# Buttons.net
KiCad netlist of a schematic drawn in Altium Designer
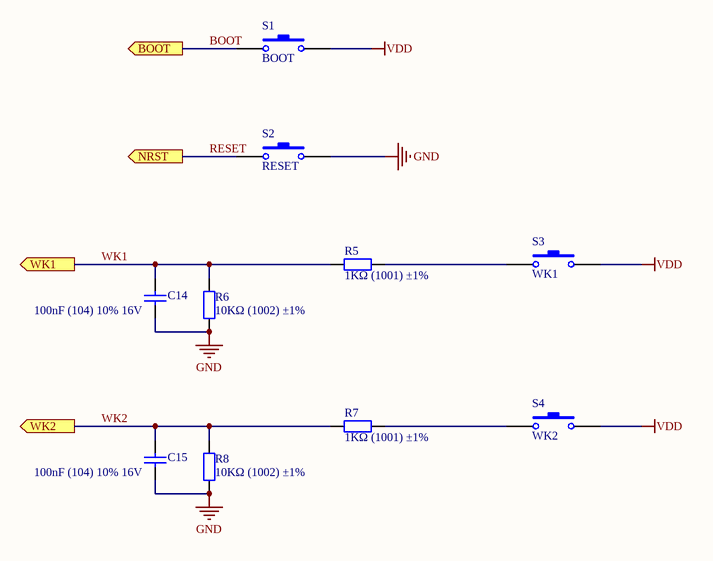
[diagram p0: Buttons.SchDoc]

(export (version "E")
  (design (tool "Eeschema 10.0.6"))
  (components
    (comp (ref "C14")
      (value "100nF (104) 10% 16V")
      (footprint "0402_C")
      (description "贴片电容")
      (libsource (lib "Miscellaneous Devices LC") (part "0402 100nF (104) 10% 16V"))
    )
    (comp (ref "C15")
      (value "100nF (104) 10% 16V")
      (footprint "0402_C")
      (description "贴片电容")
      (libsource (lib "Miscellaneous Devices LC") (part "0402 100nF (104) 10% 16V"))
    )
    (comp (ref "R5")
      (value "1KΩ (1001) ±1%")
      (footprint "0402_R")
      (description "贴片电阻")
      (libsource (lib "Miscellaneous Devices LC") (part "0402 1KΩ (1001) 1%"))
    )
    (comp (ref "R6")
      (value "10KΩ (1002) ±1%")
      (footprint "0402_R")
      (description "贴片电阻")
      (libsource (lib "Miscellaneous Devices LC") (part "0402 10KΩ (1002) 1%"))
    )
    (comp (ref "R7")
      (value "1KΩ (1001) ±1%")
      (footprint "0402_R")
      (description "贴片电阻")
      (libsource (lib "Miscellaneous Devices LC") (part "0402 1KΩ (1001) 1%"))
    )
    (comp (ref "R8")
      (value "10KΩ (1002) ±1%")
      (footprint "0402_R")
      (description "贴片电阻")
      (libsource (lib "Miscellaneous Devices LC") (part "0402 10KΩ (1002) 1%"))
    )
    (comp (ref "S1")
      (value "BOOT")
      (footprint "SW-6x6")
      (description "Switch")
      (fields (field (name "PUBLISHER") "Altium Limited"))
      (libsource (lib "Miscellaneous Devices") (part "SW-PB"))
    )
    (comp (ref "S2")
      (value "RESET")
      (footprint "SW-6x6")
      (description "Switch")
      (fields (field (name "PUBLISHER") "Altium Limited"))
      (libsource (lib "Miscellaneous Devices") (part "SW-PB"))
    )
    (comp (ref "S3")
      (value "WK1")
      (footprint "SW-6x6")
      (description "Switch")
      (fields (field (name "PUBLISHER") "Altium Limited"))
      (libsource (lib "Miscellaneous Devices") (part "SW-PB"))
    )
    (comp (ref "S4")
      (value "WK2")
      (footprint "SW-6x6")
      (description "Switch")
      (fields (field (name "PUBLISHER") "Altium Limited"))
      (libsource (lib "Miscellaneous Devices") (part "SW-PB"))
    )
  )
  (nets
    (net (code "1") (name "/BOOT") (class "Default")
      (node (ref "S1") (pin "1") (pinfunction "1_1") (pintype "passive"))
    )
    (net (code "2") (name "/RESET") (class "Default")
      (node (ref "S2") (pin "1") (pinfunction "1_1") (pintype "passive"))
    )
    (net (code "3") (name "/WK1") (class "Default")
      (node (ref "C14") (pin "2") (pinfunction "2_2") (pintype "passive"))
      (node (ref "R5") (pin "1") (pinfunction "1_1") (pintype "passive"))
      (node (ref "R6") (pin "2") (pinfunction "2_2") (pintype "passive"))
    )
    (net (code "4") (name "/WK2") (class "Default")
      (node (ref "C15") (pin "2") (pinfunction "2_2") (pintype "passive"))
      (node (ref "R7") (pin "1") (pinfunction "1_1") (pintype "passive"))
      (node (ref "R8") (pin "2") (pinfunction "2_2") (pintype "passive"))
    )
    (net (code "5") (name "GND") (class "Default")
      (node (ref "C14") (pin "1") (pinfunction "1_1") (pintype "passive"))
      (node (ref "C15") (pin "1") (pinfunction "1_1") (pintype "passive"))
      (node (ref "R6") (pin "1") (pinfunction "1_1") (pintype "passive"))
      (node (ref "R8") (pin "1") (pinfunction "1_1") (pintype "passive"))
      (node (ref "S2") (pin "2") (pinfunction "2_2") (pintype "passive"))
    )
    (net (code "6") (name "Net-(R5-Pad2)") (class "Default")
      (node (ref "R5") (pin "2") (pinfunction "2_2") (pintype "passive"))
      (node (ref "S3") (pin "1") (pinfunction "1_1") (pintype "passive"))
    )
    (net (code "7") (name "Net-(R7-Pad2)") (class "Default")
      (node (ref "R7") (pin "2") (pinfunction "2_2") (pintype "passive"))
      (node (ref "S4") (pin "1") (pinfunction "1_1") (pintype "passive"))
    )
    (net (code "8") (name "VDD") (class "Default")
      (node (ref "S1") (pin "2") (pinfunction "2_2") (pintype "passive"))
      (node (ref "S3") (pin "2") (pinfunction "2_2") (pintype "passive"))
      (node (ref "S4") (pin "2") (pinfunction "2_2") (pintype "passive"))
    )
  )
)
